# power.net
KiCad netlist of a schematic drawn in Altium Designer
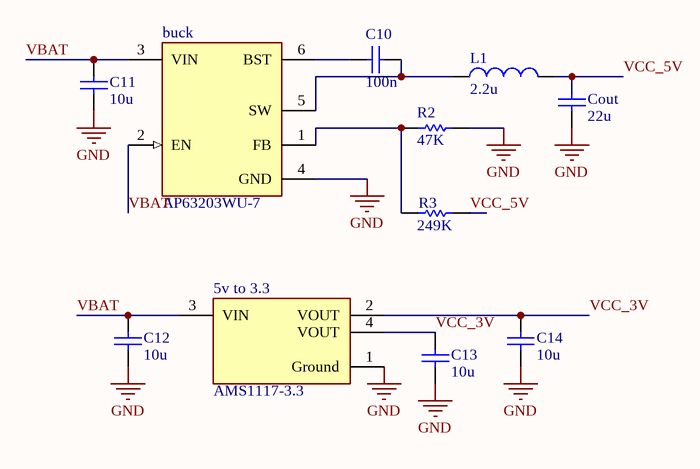
[diagram p0: power.SchDoc]

(export (version "E")
  (design (tool "Eeschema 10.0.6"))
  (components
    (comp (ref "5v to 3.3")
      (value "AMS1117-3.3")
      (footprint "FP-AMS1117-IPC_C")
      (description "LDO Voltage Regulators 1A, 3.3V")
      (fields
        (field (name "OCTOPART") "https://octopart.com/ams1117-3.3-advanced+monolithic+systems-25899300")
        (field (name "MANUFACTURER") "Advanced Monolithic Systems")
      )
      (libsource (lib "Altium Content Vault") (part "8bdbb5f8e77002000e30dd2845d0354"))
    )
    (comp (ref "buck")
      (value "AP63203WU-7")
      (footprint "FP-TSOT26-MFG")
      (description "Buck Switching Regulator IC Positive Fixed 3.3V 1 Output 2A SOT-23-6 Thin, TSOT-23-6")
      (fields (field (name "MANUFACTURER") "Diodes Inc."))
      (libsource (lib "Altium Content Vault") (part "0e61c2974d7114b43f01ef96ae2e524"))
    )
    (comp (ref "C10")
      (value "100n")
      (description "Capacitor")
      (libsource (lib "Simulation Generic Components") (part "Capacitor"))
    )
    (comp (ref "C11")
      (value "10u")
      (description "Capacitor")
      (libsource (lib "Simulation Generic Components") (part "Capacitor"))
    )
    (comp (ref "C12")
      (value "10u")
      (description "Capacitor")
      (libsource (lib "Simulation Generic Components") (part "Capacitor"))
    )
    (comp (ref "C13")
      (value "10u")
      (description "Capacitor")
      (libsource (lib "Simulation Generic Components") (part "Capacitor"))
    )
    (comp (ref "C14")
      (value "10u")
      (description "Capacitor")
      (libsource (lib "Simulation Generic Components") (part "Capacitor"))
    )
    (comp (ref "Cout")
      (value "22u")
      (description "Capacitor")
      (libsource (lib "Simulation Generic Components") (part "Capacitor"))
    )
    (comp (ref "L1")
      (value "2.2u")
      (description "Inductor")
      (libsource (lib "Simulation Generic Components") (part "Inductor"))
    )
    (comp (ref "R2")
      (value "47K")
      (description "Resistor")
      (libsource (lib "Simulation Generic Components") (part "Resistor"))
    )
    (comp (ref "R3")
      (value "249K")
      (description "Resistor")
      (libsource (lib "Simulation Generic Components") (part "Resistor"))
    )
  )
  (nets
    (net (code "1") (name "/VBAT") (class "Default")
      (node (ref "5v to 3.3") (pin "3") (pinfunction "VIN_3") (pintype "power_in"))
      (node (ref "C11") (pin "1") (pinfunction "1_1") (pintype "passive"))
      (node (ref "C12") (pin "1") (pinfunction "1_1") (pintype "passive"))
      (node (ref "buck") (pin "2") (pinfunction "EN_2") (pintype "input"))
      (node (ref "buck") (pin "3") (pinfunction "VIN_3") (pintype "power_in"))
    )
    (net (code "2") (name "/VCC_3V") (class "Default")
      (node (ref "5v to 3.3") (pin "2") (pinfunction "VOUT_2") (pintype "passive"))
      (node (ref "5v to 3.3") (pin "4") (pinfunction "VOUT_4") (pintype "passive"))
      (node (ref "C13") (pin "1") (pinfunction "1_1") (pintype "passive"))
      (node (ref "C14") (pin "1") (pinfunction "1_1") (pintype "passive"))
    )
    (net (code "3") (name "/VCC_5V") (class "Default")
      (node (ref "Cout") (pin "2") (pinfunction "2_2") (pintype "passive"))
      (node (ref "L1") (pin "2") (pinfunction "2_2") (pintype "passive"))
      (node (ref "R3") (pin "2") (pinfunction "2_2") (pintype "passive"))
    )
    (net (code "4") (name "GND") (class "Default")
      (node (ref "5v to 3.3") (pin "1") (pinfunction "Ground_1") (pintype "power_in"))
      (node (ref "C11") (pin "2") (pinfunction "2_2") (pintype "passive"))
      (node (ref "C12") (pin "2") (pinfunction "2_2") (pintype "passive"))
      (node (ref "C13") (pin "2") (pinfunction "2_2") (pintype "passive"))
      (node (ref "C14") (pin "2") (pinfunction "2_2") (pintype "passive"))
      (node (ref "Cout") (pin "1") (pinfunction "1_1") (pintype "passive"))
      (node (ref "R2") (pin "2") (pinfunction "2_2") (pintype "passive"))
      (node (ref "buck") (pin "4") (pinfunction "GND_4") (pintype "power_in"))
    )
    (net (code "5") (name "Net-(buck-BST)") (class "Default")
      (node (ref "C10") (pin "1") (pinfunction "1_1") (pintype "passive"))
      (node (ref "buck") (pin "6") (pinfunction "BST_6") (pintype "passive"))
    )
    (net (code "6") (name "Net-(buck-FB)") (class "Default")
      (node (ref "R2") (pin "1") (pinfunction "1_1") (pintype "passive"))
      (node (ref "R3") (pin "1") (pinfunction "1_1") (pintype "passive"))
      (node (ref "buck") (pin "1") (pinfunction "FB_1") (pintype "passive"))
    )
    (net (code "7") (name "Net-(buck-SW)") (class "Default")
      (node (ref "C10") (pin "2") (pinfunction "2_2") (pintype "passive"))
      (node (ref "L1") (pin "1") (pinfunction "1_1") (pintype "passive"))
      (node (ref "buck") (pin "5") (pinfunction "SW_5") (pintype "passive"))
    )
  )
)
